# TrinketBlinkM0.net
KiCad netlist of a schematic drawn in EAGLE
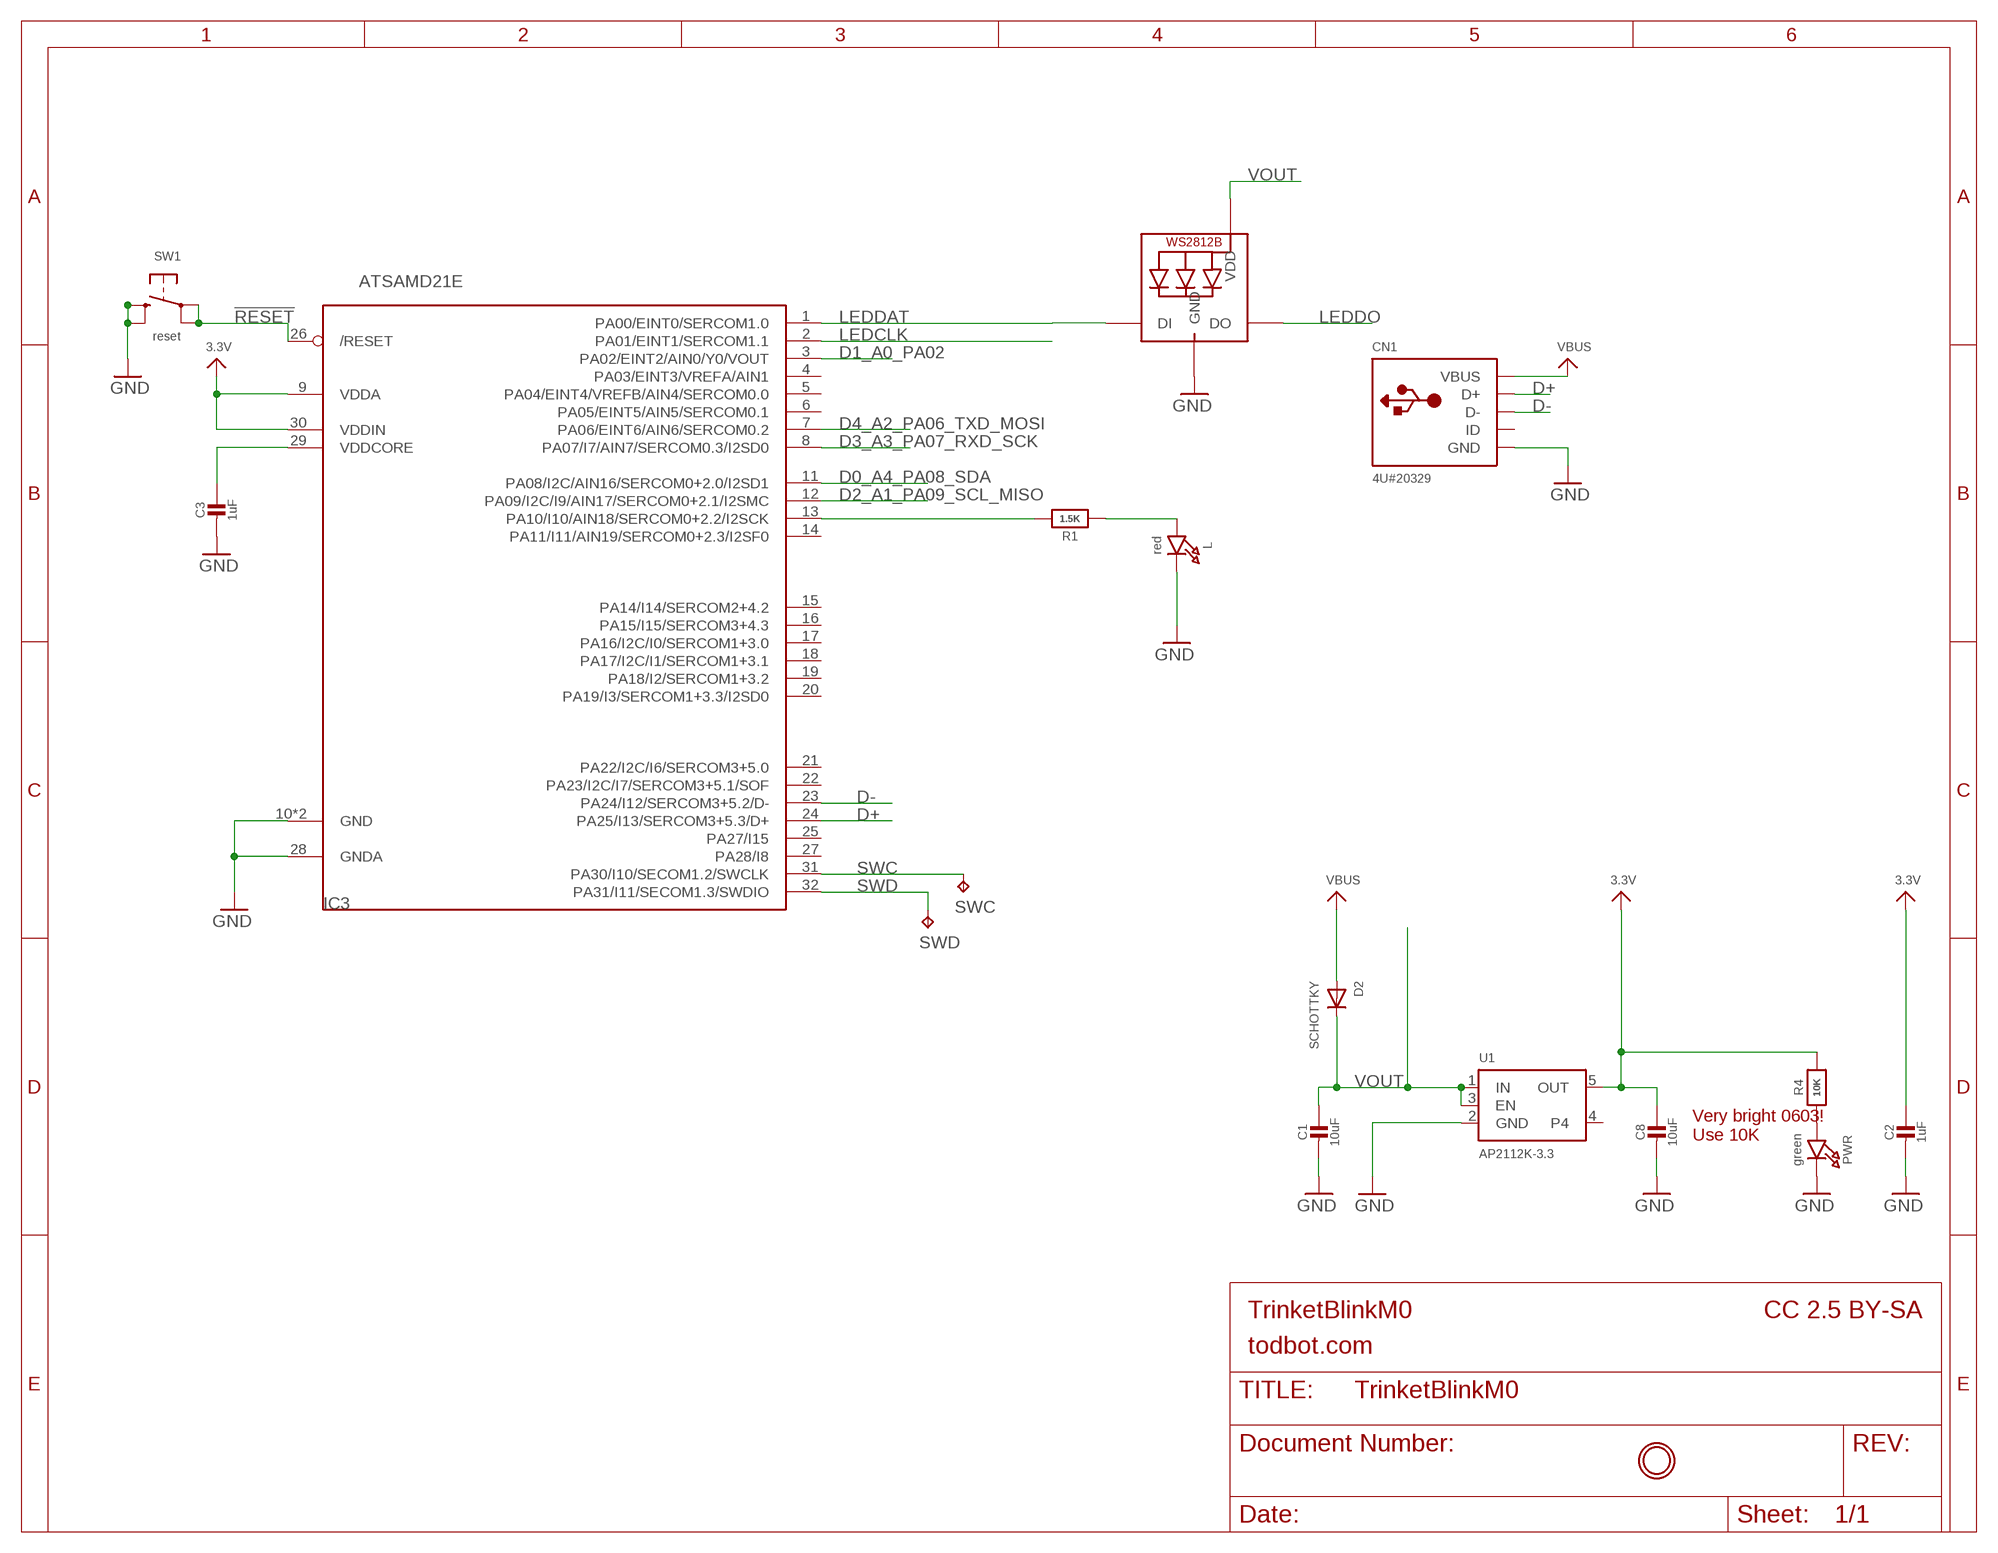
[diagram p0: schematic, sheet 1]

(export (version "E")
  (design (tool "Eeschema 10.0.6"))
  (components
    (comp (ref "C1")
      (value "10uF")
      (footprint "eagle-import:0805-NO")
      (libsource (lib "eagle-import") (part "CAP_CERAMIC0805-NOOUTLINE"))
    )
    (comp (ref "C2")
      (value "1uF")
      (footprint "eagle-import:0603-NO")
      (libsource (lib "eagle-import") (part "CAP_CERAMIC0603_NO"))
    )
    (comp (ref "C3")
      (value "1uF")
      (footprint "eagle-import:0603-NO")
      (libsource (lib "eagle-import") (part "CAP_CERAMIC0603_NO"))
    )
    (comp (ref "C8")
      (value "10uF")
      (footprint "eagle-import:0805-NO")
      (libsource (lib "eagle-import") (part "CAP_CERAMIC0805-NOOUTLINE"))
    )
    (comp (ref "CN1")
      (value "4U#20329")
      (footprint "eagle-import:4UCONN_20329_V2")
      (libsource (lib "eagle-import") (part "USB_MICRO_20329_V2"))
    )
    (comp (ref "D2")
      (value "SCHOTTKY")
      (footprint "eagle-import:SOD-123FL")
      (libsource (lib "eagle-import") (part "DIODE_SOD-123FL"))
    )
    (comp (ref "IC3")
      (value "ATSAMD21E")
      (footprint "eagle-import:QFN32_5MM")
      (libsource (lib "eagle-import") (part "ATSAMD21E"))
    )
    (comp (ref "L")
      (value "red")
      (footprint "eagle-import:CHIPLED_0603_NOOUTLINE")
      (libsource (lib "eagle-import") (part "LED0603_NOOUTLINE"))
    )
    (comp (ref "LED1")
      (value "WS2812B5050")
      (footprint "eagle-import:WS2812B")
      (libsource (lib "eagle-import") (part "WS2812B5050"))
    )
    (comp (ref "PWR")
      (value "green")
      (footprint "eagle-import:CHIPLED_0603_NOOUTLINE")
      (libsource (lib "eagle-import") (part "LED0603_NOOUTLINE"))
    )
    (comp (ref "R1")
      (value "1.5K")
      (footprint "eagle-import:0603-NO")
      (libsource (lib "eagle-import") (part "RESISTOR_0603_NOOUT"))
    )
    (comp (ref "R4")
      (value "10K")
      (footprint "eagle-import:0603-NO")
      (libsource (lib "eagle-import") (part "RESISTOR_0603_NOOUT"))
    )
    (comp (ref "SW1")
      (value "reset")
      (footprint "eagle-import:BTN_KMR2_4.6X2.8")
      (libsource (lib "eagle-import") (part "SWITCH_TACT_SMT4.6X2.8"))
    )
    (comp (ref "SWC")
      (value "TPB1,27")
      (footprint "eagle-import:B1,27")
      (libsource (lib "eagle-import") (part "TPB1,27"))
    )
    (comp (ref "SWD")
      (value "TPB1,27")
      (footprint "eagle-import:B1,27")
      (libsource (lib "eagle-import") (part "TPB1,27"))
    )
    (comp (ref "U$8")
      (value "MOUNTINGHOLE2.0")
      (footprint "eagle-import:MOUNTINGHOLE_2.0_PLATED")
      (libsource (lib "eagle-import") (part "MOUNTINGHOLE2.0"))
    )
    (comp (ref "U1")
      (value "AP2112K-3.3")
      (footprint "eagle-import:SOT23-5")
      (libsource (lib "eagle-import") (part "VREG_SOT23-5"))
    )
  )
  (nets
    (net (code "1") (name "/D+") (class "Default")
      (node (ref "CN1") (pin "D+") (pinfunction "D+_D+") (pintype "bidirectional"))
      (node (ref "IC3") (pin "24") (pinfunction "PA25/I13/SERCOM3+5.3/D+_24") (pintype "bidirectional"))
    )
    (net (code "2") (name "/D-") (class "Default")
      (node (ref "CN1") (pin "D-") (pinfunction "D-_D-") (pintype "bidirectional"))
      (node (ref "IC3") (pin "23") (pinfunction "PA24/I12/SERCOM3+5.2/D-_23") (pintype "bidirectional"))
    )
    (net (code "3") (name "/D0_A4_PA08_SDA") (class "Default")
      (node (ref "IC3") (pin "11") (pinfunction "PA08/I2C/AIN16/SERCOM0+2.0/I2SD1_11") (pintype "bidirectional"))
    )
    (net (code "4") (name "/D1_A0_PA02") (class "Default")
      (node (ref "IC3") (pin "3") (pinfunction "PA02/EINT2/AIN0/Y0/VOUT_3") (pintype "bidirectional"))
    )
    (net (code "5") (name "/D2_A1_PA09_SCL_MISO") (class "Default")
      (node (ref "IC3") (pin "12") (pinfunction "PA09/I2C/I9/AIN17/SERCOM0+2.1/I2SMC_12") (pintype "bidirectional"))
    )
    (net (code "6") (name "/D3_A3_PA07_RXD_SCK") (class "Default")
      (node (ref "IC3") (pin "8") (pinfunction "PA07/I7/AIN7/SERCOM0.3/I2SD0_8") (pintype "bidirectional"))
    )
    (net (code "7") (name "/D4_A2_PA06_TXD_MOSI") (class "Default")
      (node (ref "IC3") (pin "7") (pinfunction "PA06/EINT6/AIN6/SERCOM0.2_7") (pintype "bidirectional"))
    )
    (net (code "8") (name "/LEDCLK") (class "Default")
      (node (ref "IC3") (pin "2") (pinfunction "PA01/EINT1/SERCOM1.1_2") (pintype "bidirectional"))
    )
    (net (code "9") (name "/LEDDAT") (class "Default")
      (node (ref "IC3") (pin "1") (pinfunction "PA00/EINT0/SERCOM1.0_1") (pintype "bidirectional"))
      (node (ref "LED1") (pin "4-DIN") (pinfunction "DI_4-DIN") (pintype "input"))
    )
    (net (code "10") (name "/LEDDO") (class "Default")
      (node (ref "LED1") (pin "2-DOUT") (pinfunction "DO_2-DOUT") (pintype "output"))
    )
    (net (code "11") (name "/SWC") (class "Default")
      (node (ref "IC3") (pin "31") (pinfunction "PA30/I10/SECOM1.2/SWCLK_31") (pintype "bidirectional"))
      (node (ref "SWC") (pin "TP") (pinfunction "TP_TP") (pintype "input"))
    )
    (net (code "12") (name "/SWD") (class "Default")
      (node (ref "IC3") (pin "32") (pinfunction "PA31/I11/SECOM1.3/SWDIO_32") (pintype "bidirectional"))
      (node (ref "SWD") (pin "TP") (pinfunction "TP_TP") (pintype "input"))
    )
    (net (code "13") (name "/VOUT") (class "Default")
      (node (ref "C1") (pin "1") (pinfunction "1_1") (pintype "passive"))
      (node (ref "D2") (pin "C") (pinfunction "C_C") (pintype "passive"))
      (node (ref "LED1") (pin "1-VDD") (pinfunction "VDD_1-VDD") (pintype "power_in"))
      (node (ref "U1") (pin "1") (pinfunction "IN_1") (pintype "power_in"))
      (node (ref "U1") (pin "3") (pinfunction "EN_3") (pintype "input"))
    )
    (net (code "14") (name "/~{RESET}") (class "Default")
      (node (ref "IC3") (pin "26") (pinfunction "/RESET_26") (pintype "bidirectional"))
      (node (ref "SW1") (pin "A") (pinfunction "P_A") (pintype "passive"))
      (node (ref "SW1") (pin "A'") (pinfunction "P1_A'") (pintype "passive"))
    )
    (net (code "15") (name "3.3V") (class "Default")
      (node (ref "C2") (pin "1") (pinfunction "1_1") (pintype "passive"))
      (node (ref "C8") (pin "1") (pinfunction "1_1") (pintype "passive"))
      (node (ref "IC3") (pin "30") (pinfunction "VDDIN_30") (pintype "power_in"))
      (node (ref "IC3") (pin "9") (pinfunction "VDDA_9") (pintype "power_in"))
      (node (ref "R4") (pin "2") (pinfunction "2_2") (pintype "passive"))
      (node (ref "U1") (pin "5") (pinfunction "OUT_5") (pintype "power_in"))
    )
    (net (code "16") (name "GND") (class "Default")
      (node (ref "C1") (pin "2") (pinfunction "2_2") (pintype "passive"))
      (node (ref "C2") (pin "2") (pinfunction "2_2") (pintype "passive"))
      (node (ref "C3") (pin "2") (pinfunction "2_2") (pintype "passive"))
      (node (ref "C8") (pin "2") (pinfunction "2_2") (pintype "passive"))
      (node (ref "CN1") (pin "BASE@1") (pinfunction "GND_BASE@1") (pintype "power_in"))
      (node (ref "CN1") (pin "BASE@2") (pinfunction "GND_BASE@2") (pintype "power_in"))
      (node (ref "CN1") (pin "GND") (pinfunction "GND_GND") (pintype "power_in"))
      (node (ref "CN1") (pin "SPRT@1") (pinfunction "GND_SPRT@1") (pintype "power_in"))
      (node (ref "CN1") (pin "SPRT@2") (pinfunction "GND_SPRT@2") (pintype "power_in"))
      (node (ref "CN1") (pin "SPRT@3") (pinfunction "GND_SPRT@3") (pintype "power_in"))
      (node (ref "CN1") (pin "SPRT@4") (pinfunction "GND_SPRT@4") (pintype "power_in"))
      (node (ref "IC3") (pin "10") (pinfunction "GND_10") (pintype "power_in"))
      (node (ref "IC3") (pin "28") (pinfunction "GNDA_28") (pintype "power_in"))
      (node (ref "IC3") (pin "33") (pinfunction "GND_33") (pintype "power_in"))
      (node (ref "L") (pin "C") (pinfunction "C_C") (pintype "passive"))
      (node (ref "LED1") (pin "3-GND") (pinfunction "GND_3-GND") (pintype "power_in"))
      (node (ref "PWR") (pin "C") (pinfunction "C_C") (pintype "passive"))
      (node (ref "SW1") (pin "B") (pinfunction "S_B") (pintype "passive"))
      (node (ref "SW1") (pin "B'") (pinfunction "S1_B'") (pintype "passive"))
      (node (ref "U1") (pin "2") (pinfunction "GND_2") (pintype "power_in"))
    )
    (net (code "17") (name "Net-(IC3-PA10{slash}I10{slash}AIN18{slash}SERCOM0+2.2{slash}I2SCK)") (class "Default")
      (node (ref "IC3") (pin "13") (pinfunction "PA10/I10/AIN18/SERCOM0+2.2/I2SCK_13") (pintype "bidirectional"))
      (node (ref "R1") (pin "2") (pinfunction "2_2") (pintype "passive"))
    )
    (net (code "18") (name "Net-(IC3-VDDCORE)") (class "Default")
      (node (ref "C3") (pin "1") (pinfunction "1_1") (pintype "passive"))
      (node (ref "IC3") (pin "29") (pinfunction "VDDCORE_29") (pintype "power_in"))
    )
    (net (code "19") (name "Net-(L-PadA)") (class "Default")
      (node (ref "L") (pin "A") (pinfunction "A_A") (pintype "passive"))
      (node (ref "R1") (pin "1") (pinfunction "1_1") (pintype "passive"))
    )
    (net (code "20") (name "Net-(PWR-PadA)") (class "Default")
      (node (ref "PWR") (pin "A") (pinfunction "A_A") (pintype "passive"))
      (node (ref "R4") (pin "1") (pinfunction "1_1") (pintype "passive"))
    )
    (net (code "21") (name "VBUS") (class "Default")
      (node (ref "CN1") (pin "VBUS") (pinfunction "VBUS_VBUS") (pintype "power_in"))
      (node (ref "D2") (pin "A") (pinfunction "A_A") (pintype "passive"))
    )
    (net (code "22") (name "unconnected-(CN1-PadID)") (class "Default")
      (node (ref "CN1") (pin "ID") (pinfunction "ID_ID") (pintype "bidirectional"))
    )
    (net (code "23") (name "unconnected-(IC3-PA03{slash}EINT3{slash}VREFA{slash}AIN1-Pad4)") (class "Default")
      (node (ref "IC3") (pin "4") (pinfunction "PA03/EINT3/VREFA/AIN1_4") (pintype "bidirectional"))
    )
    (net (code "24") (name "unconnected-(IC3-PA04{slash}EINT4{slash}VREFB{slash}AIN4{slash}SERCOM0.0-Pad5)") (class "Default")
      (node (ref "IC3") (pin "5") (pinfunction "PA04/EINT4/VREFB/AIN4/SERCOM0.0_5") (pintype "bidirectional"))
    )
    (net (code "25") (name "unconnected-(IC3-PA05{slash}EINT5{slash}AIN5{slash}SERCOM0.1-Pad6)") (class "Default")
      (node (ref "IC3") (pin "6") (pinfunction "PA05/EINT5/AIN5/SERCOM0.1_6") (pintype "bidirectional"))
    )
    (net (code "26") (name "unconnected-(IC3-PA11{slash}I11{slash}AIN19{slash}SERCOM0+2.3{slash}I2SF0-Pad14)") (class "Default")
      (node (ref "IC3") (pin "14") (pinfunction "PA11/I11/AIN19/SERCOM0+2.3/I2SF0_14") (pintype "bidirectional"))
    )
    (net (code "27") (name "unconnected-(IC3-PA14{slash}I14{slash}SERCOM2+4.2-Pad15)") (class "Default")
      (node (ref "IC3") (pin "15") (pinfunction "PA14/I14/SERCOM2+4.2_15") (pintype "bidirectional"))
    )
    (net (code "28") (name "unconnected-(IC3-PA15{slash}I15{slash}SERCOM3+4.3-Pad16)") (class "Default")
      (node (ref "IC3") (pin "16") (pinfunction "PA15/I15/SERCOM3+4.3_16") (pintype "bidirectional"))
    )
    (net (code "29") (name "unconnected-(IC3-PA16{slash}I2C{slash}I0{slash}SERCOM1+3.0-Pad17)") (class "Default")
      (node (ref "IC3") (pin "17") (pinfunction "PA16/I2C/I0/SERCOM1+3.0_17") (pintype "bidirectional"))
    )
    (net (code "30") (name "unconnected-(IC3-PA17{slash}I2C{slash}I1{slash}SERCOM1+3.1-Pad18)") (class "Default")
      (node (ref "IC3") (pin "18") (pinfunction "PA17/I2C/I1/SERCOM1+3.1_18") (pintype "bidirectional"))
    )
    (net (code "31") (name "unconnected-(IC3-PA18{slash}I2{slash}SERCOM1+3.2-Pad19)") (class "Default")
      (node (ref "IC3") (pin "19") (pinfunction "PA18/I2/SERCOM1+3.2_19") (pintype "bidirectional"))
    )
    (net (code "32") (name "unconnected-(IC3-PA19{slash}I3{slash}SERCOM1+3.3{slash}I2SD0-Pad20)") (class "Default")
      (node (ref "IC3") (pin "20") (pinfunction "PA19/I3/SERCOM1+3.3/I2SD0_20") (pintype "bidirectional"))
    )
    (net (code "33") (name "unconnected-(IC3-PA22{slash}I2C{slash}I6{slash}SERCOM3+5.0-Pad21)") (class "Default")
      (node (ref "IC3") (pin "21") (pinfunction "PA22/I2C/I6/SERCOM3+5.0_21") (pintype "bidirectional"))
    )
    (net (code "34") (name "unconnected-(IC3-PA23{slash}I2C{slash}I7{slash}SERCOM3+5.1{slash}SOF-Pad22)") (class "Default")
      (node (ref "IC3") (pin "22") (pinfunction "PA23/I2C/I7/SERCOM3+5.1/SOF_22") (pintype "bidirectional"))
    )
    (net (code "35") (name "unconnected-(IC3-PA27{slash}I15-Pad25)") (class "Default")
      (node (ref "IC3") (pin "25") (pinfunction "PA27/I15_25") (pintype "bidirectional"))
    )
    (net (code "36") (name "unconnected-(IC3-PA28{slash}I8-Pad27)") (class "Default")
      (node (ref "IC3") (pin "27") (pinfunction "PA28/I8_27") (pintype "bidirectional"))
    )
    (net (code "37") (name "unconnected-(U1-P4-Pad4)") (class "Default")
      (node (ref "U1") (pin "4") (pinfunction "P4_4") (pintype "bidirectional"))
    )
  )
)
